# esp8266.net
KiCad netlist of a schematic drawn in EAGLE
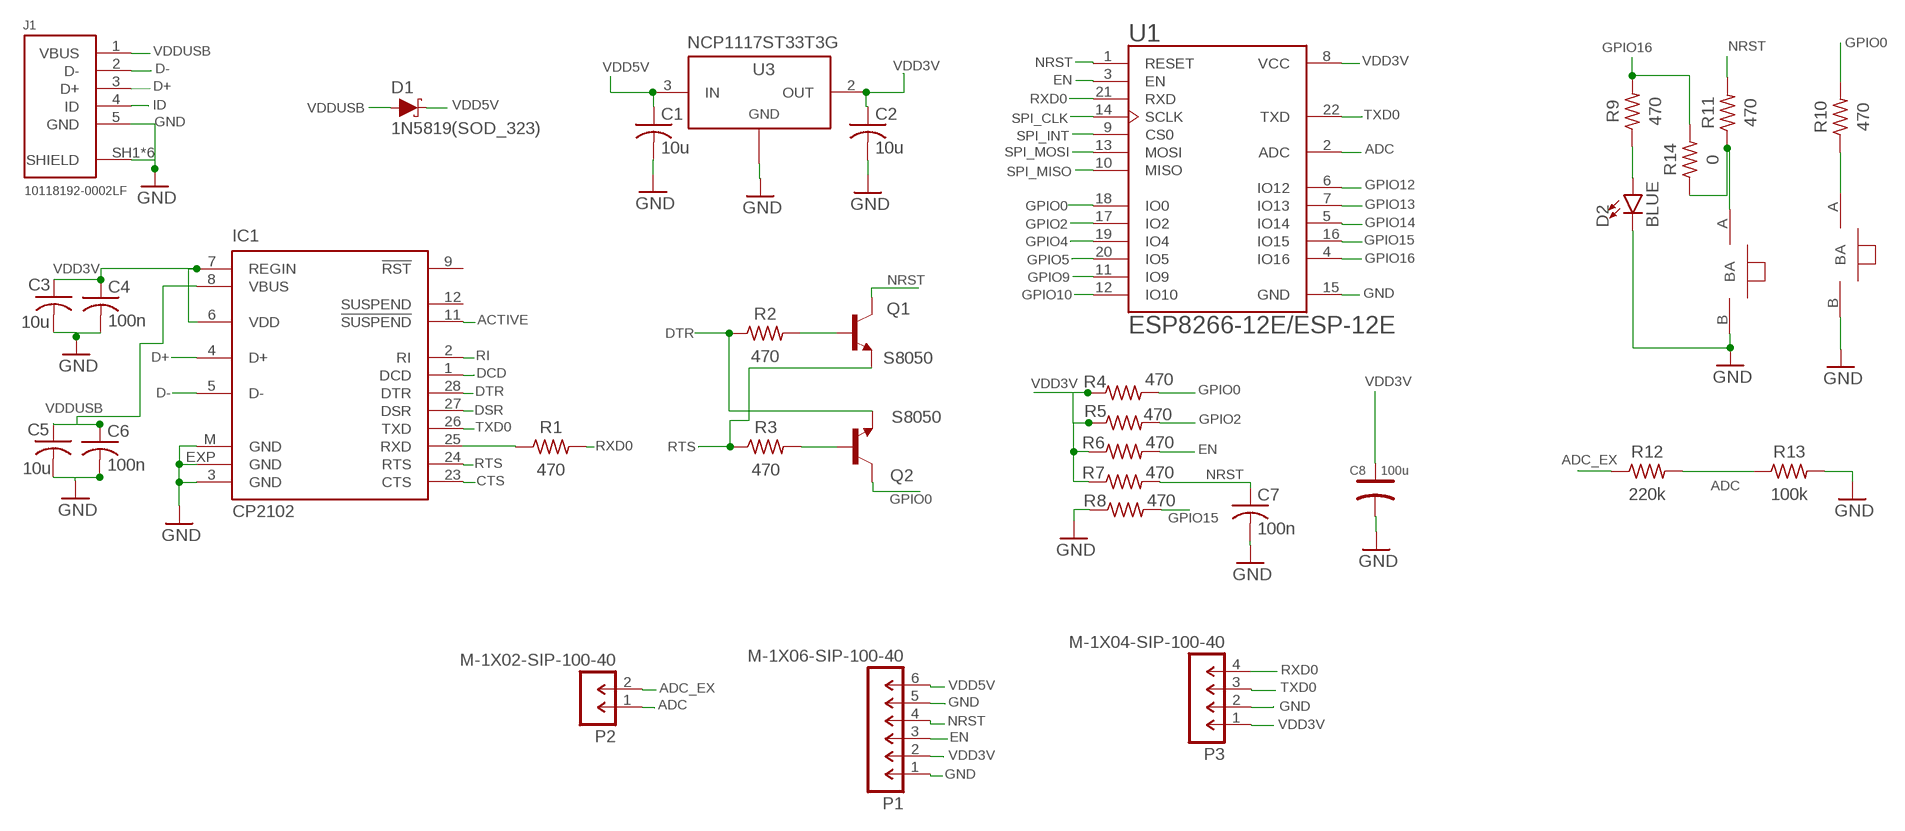
[diagram p0: schematic, sheet 1]

(export (version "E")
  (design (tool "Eeschema 10.0.6"))
  (components
    (comp (ref "C1")
      (value "10u")
      (footprint "eagle-import:CAPC2012X110")
      (libsource (lib "eagle-import") (part "C-USCHIP-0805(2012-METRIC)_"))
    )
    (comp (ref "C2")
      (value "10u")
      (footprint "eagle-import:CAPC1005X60")
      (libsource (lib "eagle-import") (part "C-USCHIP-0402(1005-METRIC)_"))
    )
    (comp (ref "C3")
      (value "10u")
      (footprint "eagle-import:CAPC1005X60")
      (libsource (lib "eagle-import") (part "C-USCHIP-0402(1005-METRIC)_"))
    )
    (comp (ref "C4")
      (value "100n")
      (footprint "eagle-import:CAPC1005X60")
      (libsource (lib "eagle-import") (part "C-USCHIP-0402(1005-METRIC)_"))
    )
    (comp (ref "C5")
      (value "10u")
      (footprint "eagle-import:CAPC1005X60")
      (libsource (lib "eagle-import") (part "C-USCHIP-0402(1005-METRIC)_"))
    )
    (comp (ref "C6")
      (value "100n")
      (footprint "eagle-import:CAPC1005X60")
      (libsource (lib "eagle-import") (part "C-USCHIP-0402(1005-METRIC)_"))
    )
    (comp (ref "C7")
      (value "100n")
      (footprint "eagle-import:CAPC1005X60")
      (libsource (lib "eagle-import") (part "C-USCHIP-0402(1005-METRIC)_"))
    )
    (comp (ref "C8")
      (value "100u")
      (footprint "eagle-import:AVX-B")
      (fields (field (name "MF") "AVX Interconnect / Elco") (field (name "MP") "TAJB107M006RNJ"))
      (libsource (lib "eagle-import") (part "TANTALUM-SMD-100UF-6.3V(AVX-B)"))
    )
    (comp (ref "D1")
      (value "1N5819(SOD_323)")
      (footprint "eagle-import:SOD-323")
      (libsource (lib "eagle-import") (part "DIODE-SCHOTTKY-BAT20J"))
    )
    (comp (ref "D2")
      (value "BLUE")
      (footprint "eagle-import:LED-0603")
      (libsource (lib "eagle-import") (part "LED-BLUE0603"))
    )
    (comp (ref "IC1")
      (value "CP2102")
      (footprint "eagle-import:MLP28")
      (libsource (lib "eagle-import") (part "CP2102"))
    )
    (comp (ref "J1")
      (value "10118192-0002LF")
      (footprint "eagle-import:10118192-0002LF")
      (fields
        (field (name "DIGIKEY_PARTNO") "609-5379-2-ND")
        (field (name "MANUFACTURER") "Amphenol ICC (FCI)")
        (field (name "CREATED_BY") "PCBLayout.com")
      )
      (libsource (lib "eagle-import") (part "10118192-0002LF"))
    )
    (comp (ref "P1")
      (value "M-1X06-SIP-100-40")
      (footprint "eagle-import:SIP-100-06-40")
      (libsource (lib "eagle-import") (part "M-1X06-SIP-100-40"))
    )
    (comp (ref "P2")
      (value "M-1X02-SIP-100-40")
      (footprint "eagle-import:SIP-100-02-40")
      (libsource (lib "eagle-import") (part "M-1X02-SIP-100-40"))
    )
    (comp (ref "P3")
      (value "M-1X04-SIP-100-40")
      (footprint "eagle-import:SIP-100-04-40")
      (libsource (lib "eagle-import") (part "M-1X04-SIP-100-40"))
    )
    (comp (ref "Q1")
      (value "S8050")
      (footprint "eagle-import:SOT23")
      (libsource (lib "eagle-import") (part "BCX70SMD"))
    )
    (comp (ref "Q2")
      (value "S8050")
      (footprint "eagle-import:SOT23")
      (libsource (lib "eagle-import") (part "BCX70SMD"))
    )
    (comp (ref "R1")
      (value "470")
      (footprint "eagle-import:RESC1005X40")
      (libsource (lib "eagle-import") (part "R-USCHIP-0402(1005-METRIC)_"))
    )
    (comp (ref "R2")
      (value "470")
      (footprint "eagle-import:RESC1005X40")
      (libsource (lib "eagle-import") (part "R-USCHIP-0402(1005-METRIC)_"))
    )
    (comp (ref "R3")
      (value "470")
      (footprint "eagle-import:RESC1005X40")
      (libsource (lib "eagle-import") (part "R-USCHIP-0402(1005-METRIC)_"))
    )
    (comp (ref "R4")
      (value "470")
      (footprint "eagle-import:RESC1005X40")
      (libsource (lib "eagle-import") (part "R-USCHIP-0402(1005-METRIC)_"))
    )
    (comp (ref "R5")
      (value "470")
      (footprint "eagle-import:RESC1005X40")
      (libsource (lib "eagle-import") (part "R-USCHIP-0402(1005-METRIC)_"))
    )
    (comp (ref "R6")
      (value "470")
      (footprint "eagle-import:RESC1005X40")
      (libsource (lib "eagle-import") (part "R-USCHIP-0402(1005-METRIC)_"))
    )
    (comp (ref "R7")
      (value "470")
      (footprint "eagle-import:RESC1005X40")
      (libsource (lib "eagle-import") (part "R-USCHIP-0402(1005-METRIC)_"))
    )
    (comp (ref "R8")
      (value "470")
      (footprint "eagle-import:RESC1005X40")
      (libsource (lib "eagle-import") (part "R-USCHIP-0402(1005-METRIC)_"))
    )
    (comp (ref "R9")
      (value "470")
      (footprint "eagle-import:RESC1005X40")
      (libsource (lib "eagle-import") (part "R-USCHIP-0402(1005-METRIC)_"))
    )
    (comp (ref "R10")
      (value "470")
      (footprint "eagle-import:RESC1005X40")
      (libsource (lib "eagle-import") (part "R-USCHIP-0402(1005-METRIC)_"))
    )
    (comp (ref "R11")
      (value "470")
      (footprint "eagle-import:RESC1005X40")
      (libsource (lib "eagle-import") (part "R-USCHIP-0402(1005-METRIC)_"))
    )
    (comp (ref "R12")
      (value "220k")
      (footprint "eagle-import:RESC1005X40")
      (libsource (lib "eagle-import") (part "R-USCHIP-0402(1005-METRIC)_"))
    )
    (comp (ref "R13")
      (value "100k")
      (footprint "eagle-import:RESC1005X40")
      (libsource (lib "eagle-import") (part "R-USCHIP-0402(1005-METRIC)_"))
    )
    (comp (ref "R14")
      (value "0")
      (footprint "eagle-import:RESC1005X40")
      (libsource (lib "eagle-import") (part "R-USCHIP-0402(1005-METRIC)_"))
    )
    (comp (ref "U$2")
      (value "PT_820")
      (footprint "eagle-import:PT_820")
      (libsource (lib "eagle-import") (part "PT_820"))
    )
    (comp (ref "U$3")
      (value "PT_820")
      (footprint "eagle-import:PT_820")
      (libsource (lib "eagle-import") (part "PT_820"))
    )
    (comp (ref "U1")
      (value "ESP8266-12E/ESP-12E")
      (footprint "eagle-import:XCVR_ESP8266-12E_ESP-12E")
      (fields (field (name "MF") "AI-Thinker"))
      (libsource (lib "eagle-import") (part "ESP8266-12E/ESP-12E"))
    )
    (comp (ref "U3")
      (value "NCP1117ST33T3G")
      (footprint "eagle-import:SOT-223")
      (fields
        (field (name "DIGIKEY_PART_NUMBER") "NCP1117ST33T3GOSTR-ND")
        (field (name "MANUFACTURER") "ON Semiconductor")
        (field (name "CREATED_BY") "PCBLayout.com")
      )
      (libsource (lib "eagle-import") (part "NCP1117ST33T3G"))
    )
  )
  (nets
    (net (code "1") (name "/ACTIVE") (class "Default")
      (node (ref "IC1") (pin "11") (pinfunction "~{SUSPEND}_11") (pintype "output"))
    )
    (net (code "2") (name "/ADC") (class "Default")
      (node (ref "P2") (pin "1") (pinfunction "1_1") (pintype "passive"))
      (node (ref "R12") (pin "2") (pinfunction "2_2") (pintype "passive"))
      (node (ref "R13") (pin "1") (pinfunction "1_1") (pintype "passive"))
      (node (ref "U1") (pin "2") (pinfunction "ADC_2") (pintype "passive"))
    )
    (net (code "3") (name "/ADC_EX") (class "Default")
      (node (ref "P2") (pin "2") (pinfunction "2_2") (pintype "passive"))
      (node (ref "R12") (pin "1") (pinfunction "1_1") (pintype "passive"))
    )
    (net (code "4") (name "/CTS") (class "Default")
      (node (ref "IC1") (pin "23") (pinfunction "CTS_23") (pintype "input"))
    )
    (net (code "5") (name "/D+") (class "Default")
      (node (ref "IC1") (pin "4") (pinfunction "D+_4") (pintype "bidirectional"))
      (node (ref "J1") (pin "3") (pinfunction "D+_3") (pintype "passive"))
    )
    (net (code "6") (name "/D-") (class "Default")
      (node (ref "IC1") (pin "5") (pinfunction "D-_5") (pintype "bidirectional"))
      (node (ref "J1") (pin "2") (pinfunction "D-_2") (pintype "passive"))
    )
    (net (code "7") (name "/DCD") (class "Default")
      (node (ref "IC1") (pin "1") (pinfunction "DCD_1") (pintype "input"))
    )
    (net (code "8") (name "/DSR") (class "Default")
      (node (ref "IC1") (pin "27") (pinfunction "DSR_27") (pintype "input"))
    )
    (net (code "9") (name "/DTR") (class "Default")
      (node (ref "IC1") (pin "28") (pinfunction "DTR_28") (pintype "output"))
      (node (ref "Q2") (pin "2") (pinfunction "E_2") (pintype "passive"))
      (node (ref "R2") (pin "1") (pinfunction "1_1") (pintype "passive"))
    )
    (net (code "10") (name "/EN") (class "Default")
      (node (ref "P1") (pin "3") (pinfunction "3_3") (pintype "passive"))
      (node (ref "R6") (pin "2") (pinfunction "2_2") (pintype "passive"))
      (node (ref "U1") (pin "3") (pinfunction "EN_3") (pintype "input"))
    )
    (net (code "11") (name "/GPIO0") (class "Default")
      (node (ref "Q2") (pin "3") (pinfunction "C_3") (pintype "passive"))
      (node (ref "R10") (pin "2") (pinfunction "2_2") (pintype "passive"))
      (node (ref "R4") (pin "2") (pinfunction "2_2") (pintype "passive"))
      (node (ref "U1") (pin "18") (pinfunction "IO0_18") (pintype "bidirectional"))
    )
    (net (code "12") (name "/GPIO2") (class "Default")
      (node (ref "R5") (pin "2") (pinfunction "2_2") (pintype "passive"))
      (node (ref "U1") (pin "17") (pinfunction "IO2_17") (pintype "bidirectional"))
    )
    (net (code "13") (name "/GPIO4") (class "Default")
      (node (ref "U1") (pin "19") (pinfunction "IO4_19") (pintype "bidirectional"))
    )
    (net (code "14") (name "/GPIO5") (class "Default")
      (node (ref "U1") (pin "20") (pinfunction "IO5_20") (pintype "bidirectional"))
    )
    (net (code "15") (name "/GPIO9") (class "Default")
      (node (ref "U1") (pin "11") (pinfunction "IO9_11") (pintype "bidirectional"))
    )
    (net (code "16") (name "/GPIO10") (class "Default")
      (node (ref "U1") (pin "12") (pinfunction "IO10_12") (pintype "bidirectional"))
    )
    (net (code "17") (name "/GPIO12") (class "Default")
      (node (ref "U1") (pin "6") (pinfunction "IO12_6") (pintype "bidirectional"))
    )
    (net (code "18") (name "/GPIO13") (class "Default")
      (node (ref "U1") (pin "7") (pinfunction "IO13_7") (pintype "bidirectional"))
    )
    (net (code "19") (name "/GPIO14") (class "Default")
      (node (ref "U1") (pin "5") (pinfunction "IO14_5") (pintype "bidirectional"))
    )
    (net (code "20") (name "/GPIO15") (class "Default")
      (node (ref "R8") (pin "2") (pinfunction "2_2") (pintype "passive"))
      (node (ref "U1") (pin "16") (pinfunction "IO15_16") (pintype "bidirectional"))
    )
    (net (code "21") (name "/GPIO16") (class "Default")
      (node (ref "R14") (pin "2") (pinfunction "2_2") (pintype "passive"))
      (node (ref "R9") (pin "2") (pinfunction "2_2") (pintype "passive"))
      (node (ref "U1") (pin "4") (pinfunction "IO16_4") (pintype "bidirectional"))
    )
    (net (code "22") (name "/ID") (class "Default")
      (node (ref "J1") (pin "4") (pinfunction "ID_4") (pintype "passive"))
    )
    (net (code "23") (name "/NRST") (class "Default")
      (node (ref "C7") (pin "1") (pinfunction "1_1") (pintype "passive"))
      (node (ref "P1") (pin "4") (pinfunction "4_4") (pintype "passive"))
      (node (ref "Q1") (pin "3") (pinfunction "C_3") (pintype "passive"))
      (node (ref "R11") (pin "2") (pinfunction "2_2") (pintype "passive"))
      (node (ref "R7") (pin "2") (pinfunction "2_2") (pintype "passive"))
      (node (ref "U1") (pin "1") (pinfunction "RESET_1") (pintype "input"))
    )
    (net (code "24") (name "/RI") (class "Default")
      (node (ref "IC1") (pin "2") (pinfunction "RI_2") (pintype "input"))
    )
    (net (code "25") (name "/RTS") (class "Default")
      (node (ref "IC1") (pin "24") (pinfunction "RTS_24") (pintype "output"))
      (node (ref "Q1") (pin "2") (pinfunction "E_2") (pintype "passive"))
      (node (ref "R3") (pin "1") (pinfunction "1_1") (pintype "passive"))
    )
    (net (code "26") (name "/RXD0") (class "Default")
      (node (ref "P3") (pin "4") (pinfunction "4_4") (pintype "passive"))
      (node (ref "R1") (pin "2") (pinfunction "2_2") (pintype "passive"))
      (node (ref "U1") (pin "21") (pinfunction "RXD_21") (pintype "input"))
    )
    (net (code "27") (name "/SPI_CLK") (class "Default")
      (node (ref "U1") (pin "14") (pinfunction "SCLK_14") (pintype "input"))
    )
    (net (code "28") (name "/SPI_INT") (class "Default")
      (node (ref "U1") (pin "9") (pinfunction "CS0_9") (pintype "input"))
    )
    (net (code "29") (name "/SPI_MISO") (class "Default")
      (node (ref "U1") (pin "10") (pinfunction "MISO_10") (pintype "bidirectional"))
    )
    (net (code "30") (name "/SPI_MOSI") (class "Default")
      (node (ref "U1") (pin "13") (pinfunction "MOSI_13") (pintype "bidirectional"))
    )
    (net (code "31") (name "/TXD0") (class "Default")
      (node (ref "IC1") (pin "26") (pinfunction "TXD_26") (pintype "output"))
      (node (ref "P3") (pin "3") (pinfunction "3_3") (pintype "passive"))
      (node (ref "U1") (pin "22") (pinfunction "TXD_22") (pintype "output"))
    )
    (net (code "32") (name "/VDD3V") (class "Default")
      (node (ref "C2") (pin "1") (pinfunction "1_1") (pintype "passive"))
      (node (ref "C3") (pin "1") (pinfunction "1_1") (pintype "passive"))
      (node (ref "C4") (pin "1") (pinfunction "1_1") (pintype "passive"))
      (node (ref "C8") (pin "+") (pinfunction "+_+") (pintype "passive"))
      (node (ref "IC1") (pin "6") (pinfunction "VDD_6") (pintype "power_in"))
      (node (ref "IC1") (pin "7") (pinfunction "REGIN_7") (pintype "passive"))
      (node (ref "P1") (pin "2") (pinfunction "2_2") (pintype "passive"))
      (node (ref "P3") (pin "1") (pinfunction "1_1") (pintype "passive"))
      (node (ref "R4") (pin "1") (pinfunction "1_1") (pintype "passive"))
      (node (ref "R5") (pin "1") (pinfunction "1_1") (pintype "passive"))
      (node (ref "R6") (pin "1") (pinfunction "1_1") (pintype "passive"))
      (node (ref "R7") (pin "1") (pinfunction "1_1") (pintype "passive"))
      (node (ref "U1") (pin "8") (pinfunction "VCC_8") (pintype "power_in"))
      (node (ref "U3") (pin "2") (pinfunction "OUT_2") (pintype "output"))
      (node (ref "U3") (pin "4") (pinfunction "4_4") (pintype "passive"))
    )
    (net (code "33") (name "/VDD5V") (class "Default")
      (node (ref "C1") (pin "1") (pinfunction "1_1") (pintype "passive"))
      (node (ref "D1") (pin "C") (pinfunction "C_C") (pintype "passive"))
      (node (ref "P1") (pin "6") (pinfunction "6_6") (pintype "passive"))
      (node (ref "U3") (pin "3") (pinfunction "IN_3") (pintype "input"))
    )
    (net (code "34") (name "/VDDUSB") (class "Default")
      (node (ref "C5") (pin "1") (pinfunction "1_1") (pintype "passive"))
      (node (ref "C6") (pin "1") (pinfunction "1_1") (pintype "passive"))
      (node (ref "D1") (pin "A") (pinfunction "A_A") (pintype "passive"))
      (node (ref "IC1") (pin "8") (pinfunction "VBUS_8") (pintype "input"))
      (node (ref "J1") (pin "1") (pinfunction "VBUS_1") (pintype "passive"))
    )
    (net (code "35") (name "GND") (class "Default")
      (node (ref "C1") (pin "2") (pinfunction "2_2") (pintype "passive"))
      (node (ref "C2") (pin "2") (pinfunction "2_2") (pintype "passive"))
      (node (ref "C3") (pin "2") (pinfunction "2_2") (pintype "passive"))
      (node (ref "C4") (pin "2") (pinfunction "2_2") (pintype "passive"))
      (node (ref "C5") (pin "2") (pinfunction "2_2") (pintype "passive"))
      (node (ref "C6") (pin "2") (pinfunction "2_2") (pintype "passive"))
      (node (ref "C7") (pin "2") (pinfunction "2_2") (pintype "passive"))
      (node (ref "C8") (pin "-") (pinfunction "-_-") (pintype "passive"))
      (node (ref "D2") (pin "C") (pinfunction "C_C") (pintype "passive"))
      (node (ref "IC1") (pin "3") (pinfunction "GND_3") (pintype "power_in"))
      (node (ref "IC1") (pin "EXP") (pinfunction "GND_EXP") (pintype "power_in"))
      (node (ref "IC1") (pin "M") (pinfunction "GND_M") (pintype "power_in"))
      (node (ref "J1") (pin "5") (pinfunction "GND_5") (pintype "passive"))
      (node (ref "J1") (pin "SH1") (pinfunction "SHIELD_SH1") (pintype "power_in"))
      (node (ref "J1") (pin "SH2") (pinfunction "SHIELD_SH2") (pintype "power_in"))
      (node (ref "J1") (pin "SH3") (pinfunction "SHIELD_SH3") (pintype "power_in"))
      (node (ref "J1") (pin "SH4") (pinfunction "SHIELD_SH4") (pintype "power_in"))
      (node (ref "J1") (pin "SH5") (pinfunction "SHIELD_SH5") (pintype "power_in"))
      (node (ref "J1") (pin "SH6") (pinfunction "SHIELD_SH6") (pintype "power_in"))
      (node (ref "P1") (pin "1") (pinfunction "1_1") (pintype "passive"))
      (node (ref "P1") (pin "5") (pinfunction "5_5") (pintype "passive"))
      (node (ref "P3") (pin "2") (pinfunction "2_2") (pintype "passive"))
      (node (ref "R13") (pin "2") (pinfunction "2_2") (pintype "passive"))
      (node (ref "R8") (pin "1") (pinfunction "1_1") (pintype "passive"))
      (node (ref "U$2") (pin "B") (pinfunction "B_B") (pintype "bidirectional"))
      (node (ref "U$3") (pin "B") (pinfunction "B_B") (pintype "bidirectional"))
      (node (ref "U1") (pin "15") (pinfunction "GND_15") (pintype "power_in"))
      (node (ref "U3") (pin "1") (pinfunction "ADJ/GND_1") (pintype "power_in"))
    )
    (net (code "36") (name "Net-(D2-PadA)") (class "Default")
      (node (ref "D2") (pin "A") (pinfunction "A_A") (pintype "passive"))
      (node (ref "R9") (pin "1") (pinfunction "1_1") (pintype "passive"))
    )
    (net (code "37") (name "Net-(IC1-RXD)") (class "Default")
      (node (ref "IC1") (pin "25") (pinfunction "RXD_25") (pintype "input"))
      (node (ref "R1") (pin "1") (pinfunction "1_1") (pintype "passive"))
    )
    (net (code "38") (name "Net-(Q1-B)") (class "Default")
      (node (ref "Q1") (pin "1") (pinfunction "B_1") (pintype "passive"))
      (node (ref "R2") (pin "2") (pinfunction "2_2") (pintype "passive"))
    )
    (net (code "39") (name "Net-(Q2-B)") (class "Default")
      (node (ref "Q2") (pin "1") (pinfunction "B_1") (pintype "passive"))
      (node (ref "R3") (pin "2") (pinfunction "2_2") (pintype "passive"))
    )
    (net (code "40") (name "Net-(R10-Pad1)") (class "Default")
      (node (ref "R10") (pin "1") (pinfunction "1_1") (pintype "passive"))
      (node (ref "U$3") (pin "A") (pinfunction "A_A") (pintype "bidirectional"))
    )
    (net (code "41") (name "Net-(R11-Pad1)") (class "Default")
      (node (ref "R11") (pin "1") (pinfunction "1_1") (pintype "passive"))
      (node (ref "R14") (pin "1") (pinfunction "1_1") (pintype "passive"))
      (node (ref "U$2") (pin "A") (pinfunction "A_A") (pintype "bidirectional"))
    )
    (net (code "42") (name "unconnected-(IC1-SUSPEND-Pad12)") (class "Default")
      (node (ref "IC1") (pin "12") (pinfunction "SUSPEND_12") (pintype "output"))
    )
    (net (code "43") (name "unconnected-(IC1-~{RST}-Pad9)") (class "Default")
      (node (ref "IC1") (pin "9") (pinfunction "~{RST}_9") (pintype "bidirectional"))
    )
  )
)
